# SJA1105Q_LAN8870_EVB_revA.net
KiCad netlist of a schematic drawn in Altium Designer
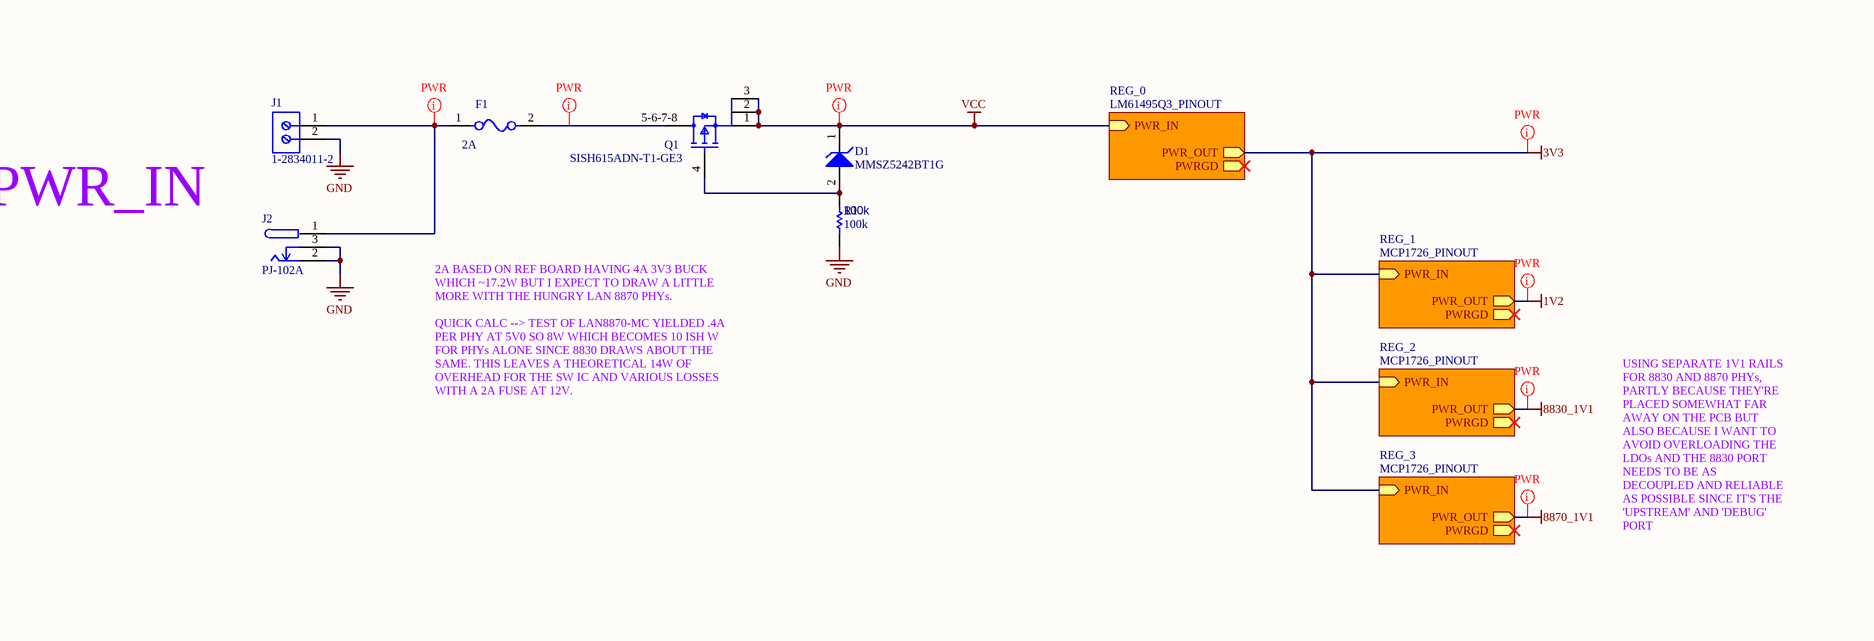
[diagram p0: SJA1105Q_LAN8870_EVB_revA.SchDoc, top left]
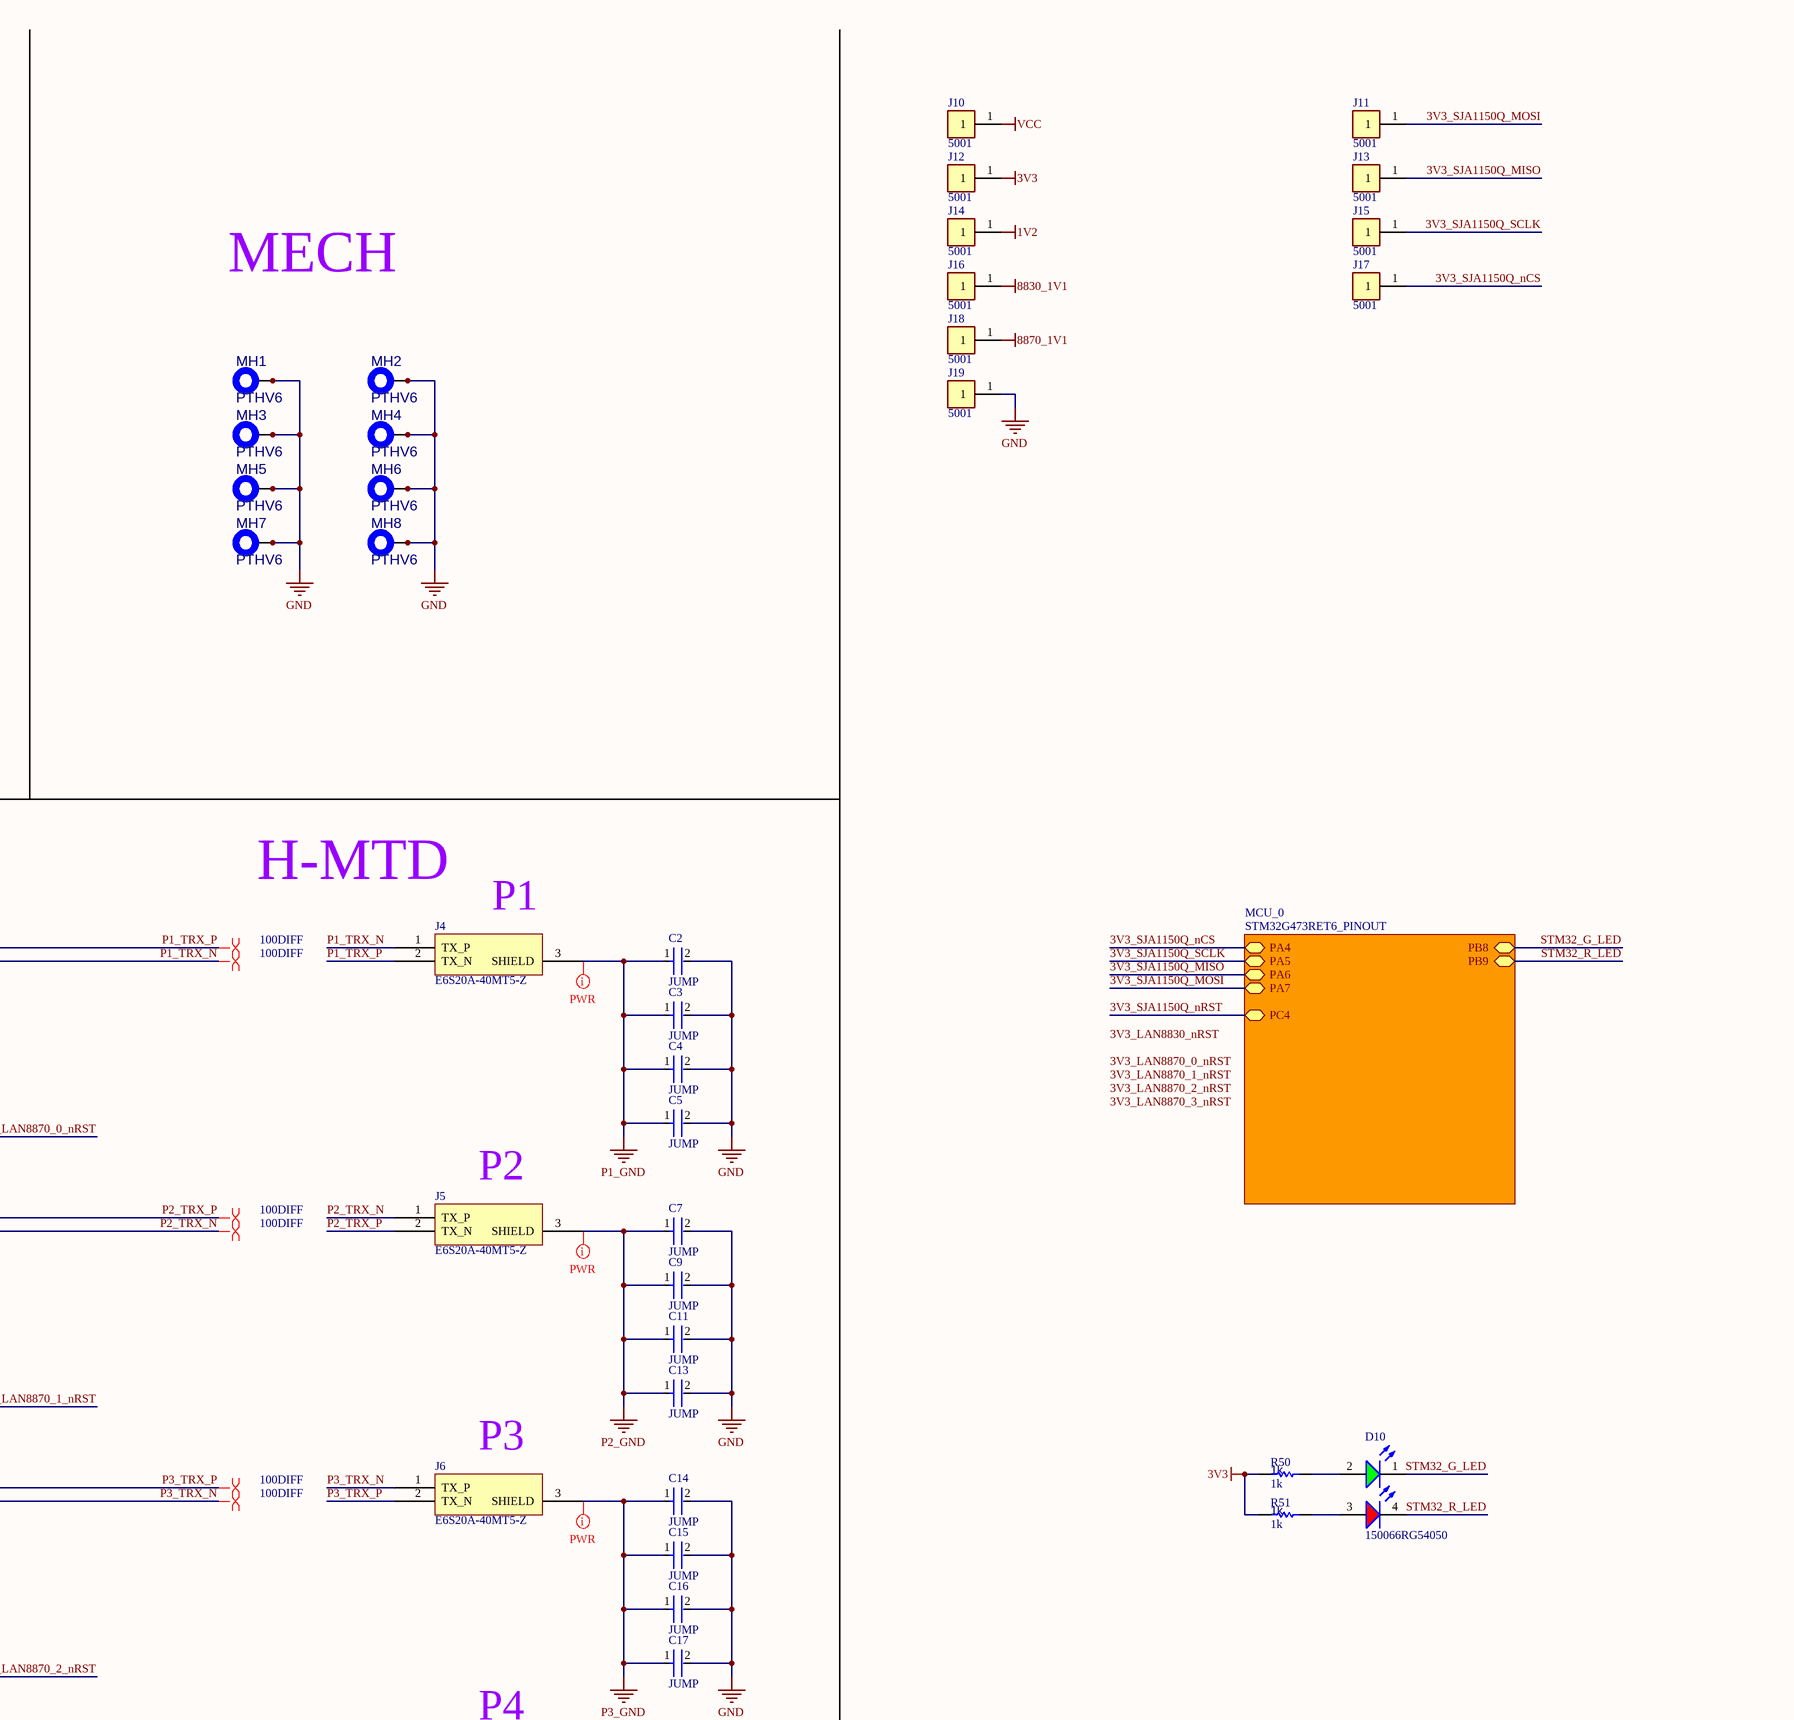
[diagram p1: SJA1105Q_LAN8870_EVB_revA.SchDoc, top right]
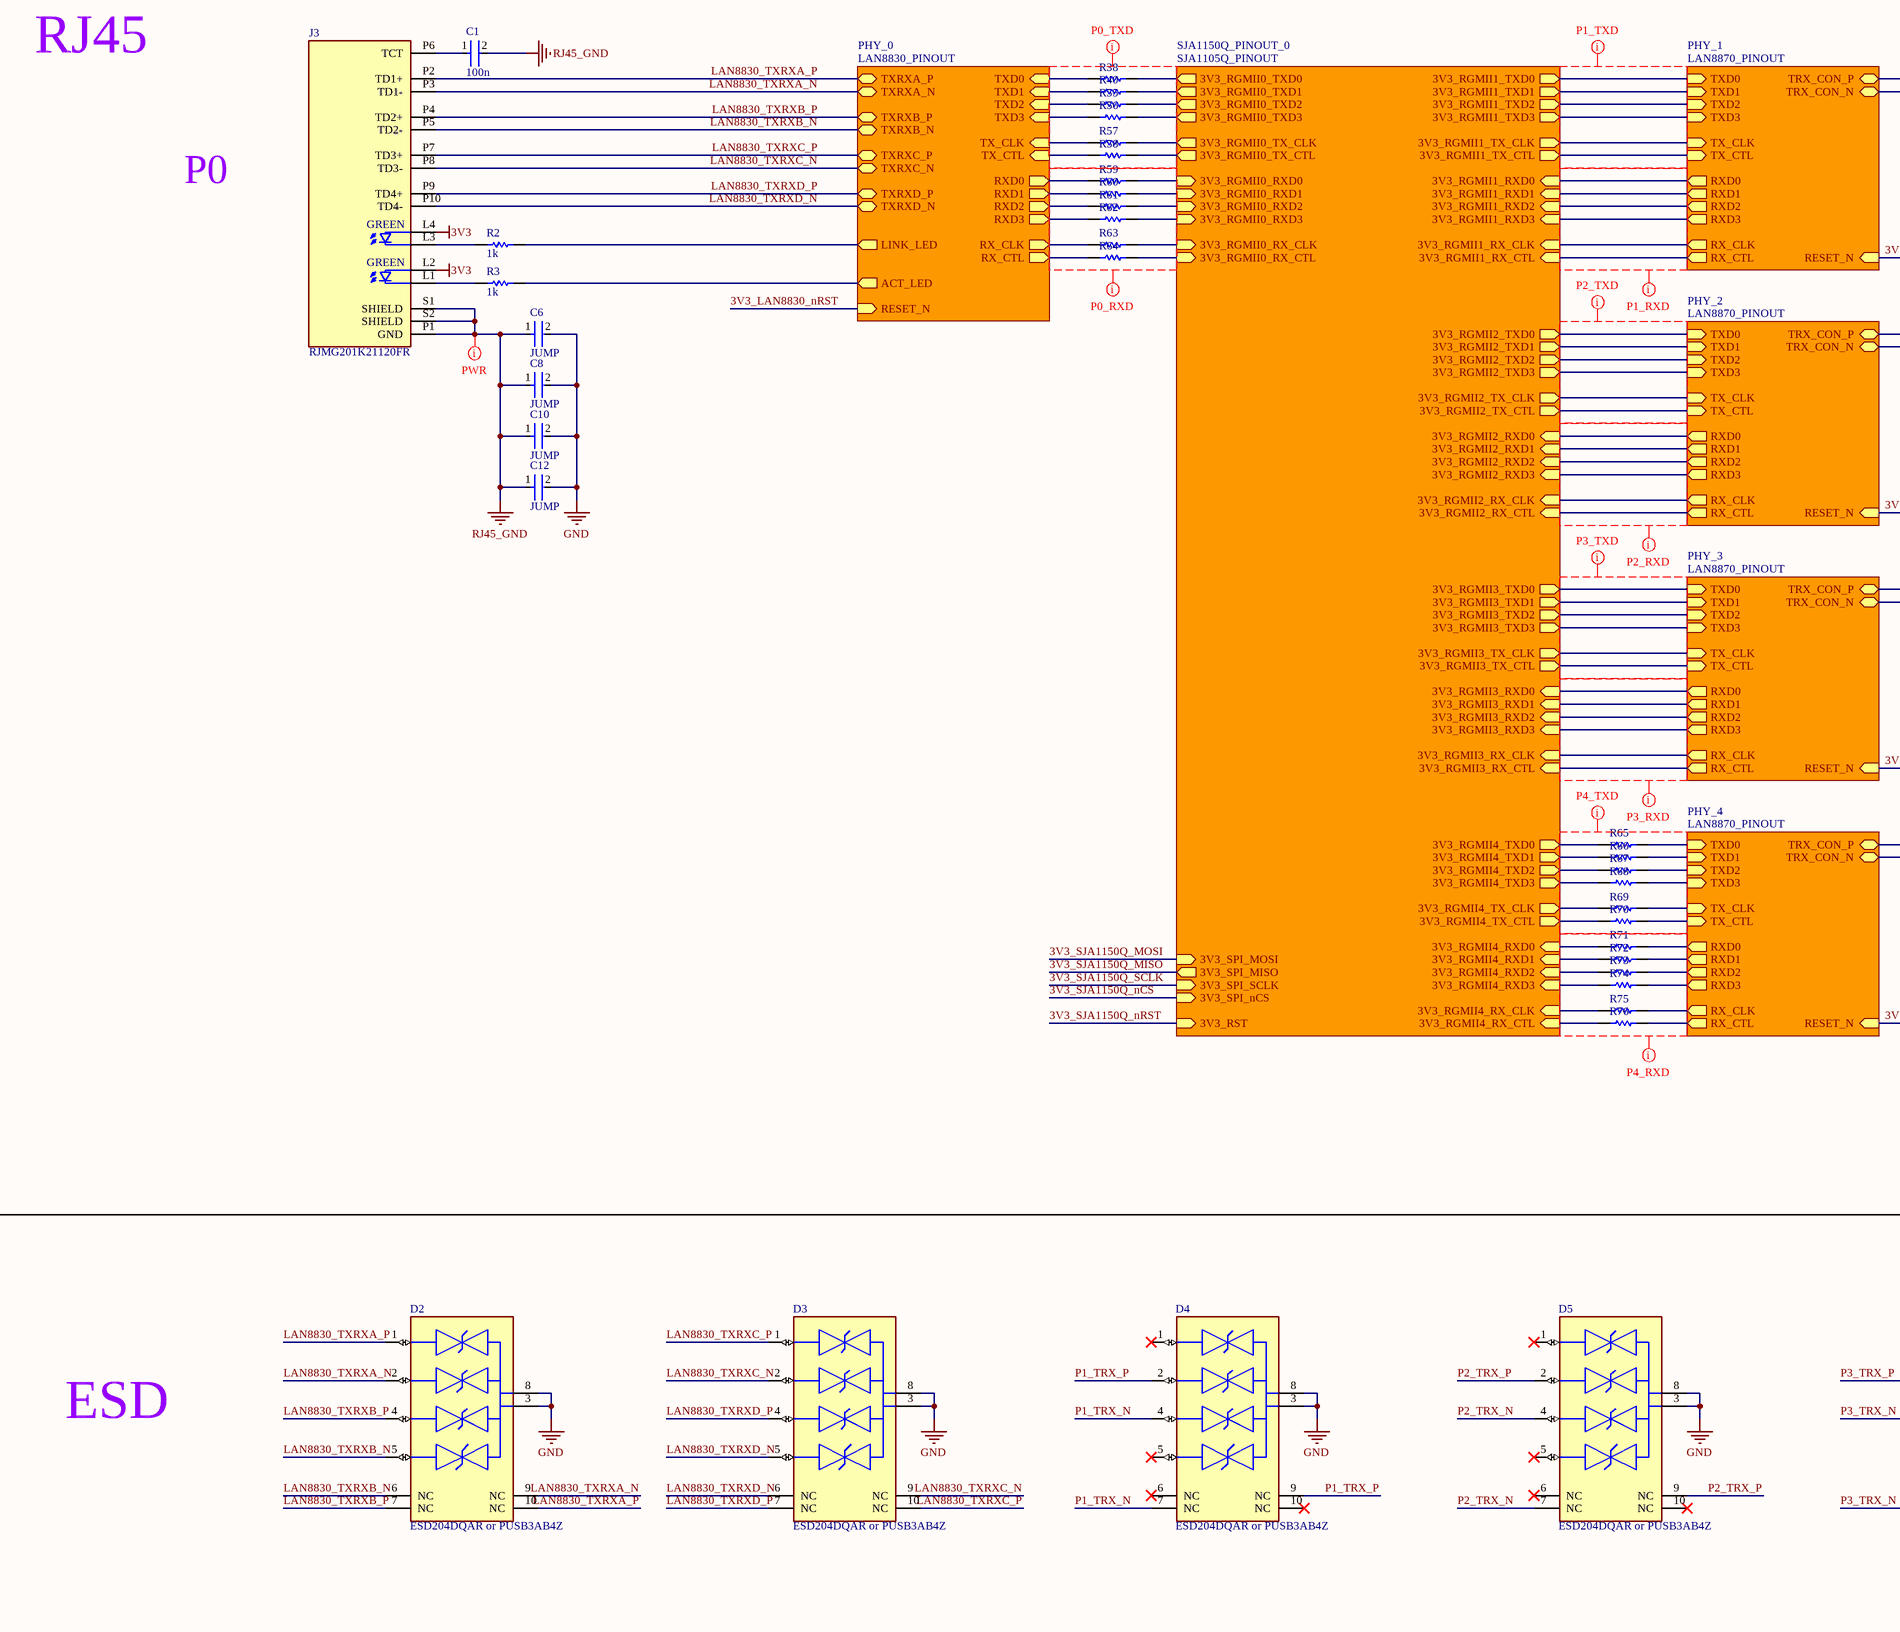
[diagram p2: SJA1105Q_LAN8870_EVB_revA.SchDoc, bottom left]
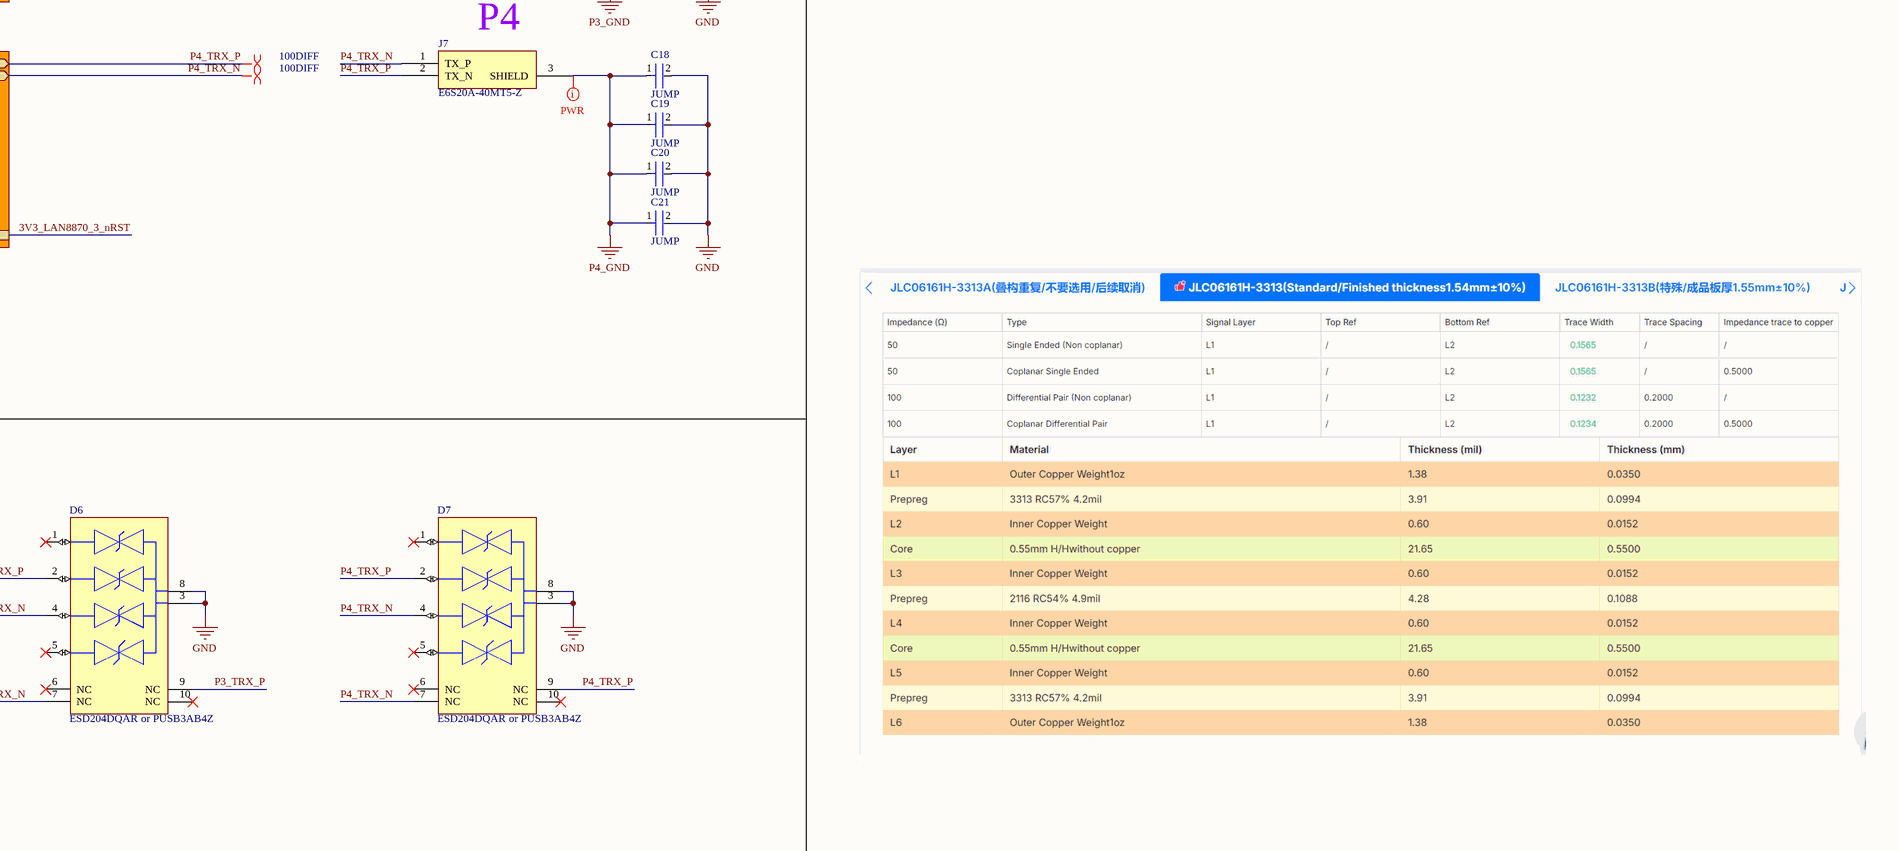
[diagram p3: SJA1105Q_LAN8870_EVB_revA.SchDoc, bottom right]

(export (version "E")
  (design (tool "Eeschema 10.0.6"))
  (components
    (comp (ref "C1")
      (value "100n")
      (footprint "FP-0402-L_1_0_0_05-W_0_5-IPC_A")
      (description "LARGE PADS, 0402 CAP, CHANGE COMMENT TO MATCH REAL P/N")
      (libsource (lib "Space Concordia") (part "b4654b650e69147ec39a6b967a45e02"))
    )
    (comp (ref "C2")
      (value "JUMP")
      (footprint "FP-0402-L_1_0_0_05-W_0_5-IPC_A")
      (description "LARGE PADS, 0402 CAP, CHANGE COMMENT TO MATCH REAL P/N")
      (libsource (lib "Space Concordia") (part "b4654b650e69147ec39a6b967a45e02"))
    )
    (comp (ref "C3")
      (value "JUMP")
      (footprint "FP-0402-L_1_0_0_05-W_0_5-IPC_A")
      (description "LARGE PADS, 0402 CAP, CHANGE COMMENT TO MATCH REAL P/N")
      (libsource (lib "Space Concordia") (part "b4654b650e69147ec39a6b967a45e02"))
    )
    (comp (ref "C4")
      (value "JUMP")
      (footprint "FP-0402-L_1_0_0_05-W_0_5-IPC_A")
      (description "LARGE PADS, 0402 CAP, CHANGE COMMENT TO MATCH REAL P/N")
      (libsource (lib "Space Concordia") (part "b4654b650e69147ec39a6b967a45e02"))
    )
    (comp (ref "C5")
      (value "JUMP")
      (footprint "FP-0402-L_1_0_0_05-W_0_5-IPC_A")
      (description "LARGE PADS, 0402 CAP, CHANGE COMMENT TO MATCH REAL P/N")
      (libsource (lib "Space Concordia") (part "b4654b650e69147ec39a6b967a45e02"))
    )
    (comp (ref "C6")
      (value "JUMP")
      (footprint "FP-0402-L_1_0_0_05-W_0_5-IPC_A")
      (description "LARGE PADS, 0402 CAP, CHANGE COMMENT TO MATCH REAL P/N")
      (libsource (lib "Space Concordia") (part "b4654b650e69147ec39a6b967a45e02"))
    )
    (comp (ref "C7")
      (value "JUMP")
      (footprint "FP-0402-L_1_0_0_05-W_0_5-IPC_A")
      (description "LARGE PADS, 0402 CAP, CHANGE COMMENT TO MATCH REAL P/N")
      (libsource (lib "Space Concordia") (part "b4654b650e69147ec39a6b967a45e02"))
    )
    (comp (ref "C8")
      (value "JUMP")
      (footprint "FP-0402-L_1_0_0_05-W_0_5-IPC_A")
      (description "LARGE PADS, 0402 CAP, CHANGE COMMENT TO MATCH REAL P/N")
      (libsource (lib "Space Concordia") (part "b4654b650e69147ec39a6b967a45e02"))
    )
    (comp (ref "C9")
      (value "JUMP")
      (footprint "FP-0402-L_1_0_0_05-W_0_5-IPC_A")
      (description "LARGE PADS, 0402 CAP, CHANGE COMMENT TO MATCH REAL P/N")
      (libsource (lib "Space Concordia") (part "b4654b650e69147ec39a6b967a45e02"))
    )
    (comp (ref "C10")
      (value "JUMP")
      (footprint "FP-0402-L_1_0_0_05-W_0_5-IPC_A")
      (description "LARGE PADS, 0402 CAP, CHANGE COMMENT TO MATCH REAL P/N")
      (libsource (lib "Space Concordia") (part "b4654b650e69147ec39a6b967a45e02"))
    )
    (comp (ref "C11")
      (value "JUMP")
      (footprint "FP-0402-L_1_0_0_05-W_0_5-IPC_A")
      (description "LARGE PADS, 0402 CAP, CHANGE COMMENT TO MATCH REAL P/N")
      (libsource (lib "Space Concordia") (part "b4654b650e69147ec39a6b967a45e02"))
    )
    (comp (ref "C12")
      (value "JUMP")
      (footprint "FP-0402-L_1_0_0_05-W_0_5-IPC_A")
      (description "LARGE PADS, 0402 CAP, CHANGE COMMENT TO MATCH REAL P/N")
      (libsource (lib "Space Concordia") (part "b4654b650e69147ec39a6b967a45e02"))
    )
    (comp (ref "C13")
      (value "JUMP")
      (footprint "FP-0402-L_1_0_0_05-W_0_5-IPC_A")
      (description "LARGE PADS, 0402 CAP, CHANGE COMMENT TO MATCH REAL P/N")
      (libsource (lib "Space Concordia") (part "b4654b650e69147ec39a6b967a45e02"))
    )
    (comp (ref "C14")
      (value "JUMP")
      (footprint "FP-0402-L_1_0_0_05-W_0_5-IPC_A")
      (description "LARGE PADS, 0402 CAP, CHANGE COMMENT TO MATCH REAL P/N")
      (libsource (lib "Space Concordia") (part "b4654b650e69147ec39a6b967a45e02"))
    )
    (comp (ref "C15")
      (value "JUMP")
      (footprint "FP-0402-L_1_0_0_05-W_0_5-IPC_A")
      (description "LARGE PADS, 0402 CAP, CHANGE COMMENT TO MATCH REAL P/N")
      (libsource (lib "Space Concordia") (part "b4654b650e69147ec39a6b967a45e02"))
    )
    (comp (ref "C16")
      (value "JUMP")
      (footprint "FP-0402-L_1_0_0_05-W_0_5-IPC_A")
      (description "LARGE PADS, 0402 CAP, CHANGE COMMENT TO MATCH REAL P/N")
      (libsource (lib "Space Concordia") (part "b4654b650e69147ec39a6b967a45e02"))
    )
    (comp (ref "C17")
      (value "JUMP")
      (footprint "FP-0402-L_1_0_0_05-W_0_5-IPC_A")
      (description "LARGE PADS, 0402 CAP, CHANGE COMMENT TO MATCH REAL P/N")
      (libsource (lib "Space Concordia") (part "b4654b650e69147ec39a6b967a45e02"))
    )
    (comp (ref "C18")
      (value "JUMP")
      (footprint "FP-0402-L_1_0_0_05-W_0_5-IPC_A")
      (description "LARGE PADS, 0402 CAP, CHANGE COMMENT TO MATCH REAL P/N")
      (libsource (lib "Space Concordia") (part "b4654b650e69147ec39a6b967a45e02"))
    )
    (comp (ref "C19")
      (value "JUMP")
      (footprint "FP-0402-L_1_0_0_05-W_0_5-IPC_A")
      (description "LARGE PADS, 0402 CAP, CHANGE COMMENT TO MATCH REAL P/N")
      (libsource (lib "Space Concordia") (part "b4654b650e69147ec39a6b967a45e02"))
    )
    (comp (ref "C20")
      (value "JUMP")
      (footprint "FP-0402-L_1_0_0_05-W_0_5-IPC_A")
      (description "LARGE PADS, 0402 CAP, CHANGE COMMENT TO MATCH REAL P/N")
      (libsource (lib "Space Concordia") (part "b4654b650e69147ec39a6b967a45e02"))
    )
    (comp (ref "C21")
      (value "JUMP")
      (footprint "FP-0402-L_1_0_0_05-W_0_5-IPC_A")
      (description "LARGE PADS, 0402 CAP, CHANGE COMMENT TO MATCH REAL P/N")
      (libsource (lib "Space Concordia") (part "b4654b650e69147ec39a6b967a45e02"))
    )
    (comp (ref "D1")
      (value "MMSZ5242BT1G")
      (footprint "ONSC-SOD-123-2-425-04_V")
      (description "Zener Voltage Regulator, 500 mW, 2-Pin SOD-123, Pb-Free, Tape and Reel")
      (fields (field (name "MANUFACTURER") "On Semiconductor"))
      (libsource (lib "Altium Content Vault") (part "ONSC-K1A2-2"))
    )
    (comp (ref "D2")
      (value "ESD204DQAR or PUSB3AB4Z")
      (footprint "FP-DQA0010A-MFG")
      (description "4-CHANNEL LOW-CAPACITANCE SURGE")
      (fields
        (field (name "MANUFACTURER") "Texas Instruments")
        (field (name "OCTOPART") "https://octopart.com/esd204dqar-texas+instruments-89917476")
      )
      (libsource (lib "Altium Content Vault") (part "1465e58c1818c7767b55926832f0bf5"))
    )
    (comp (ref "D3")
      (value "ESD204DQAR or PUSB3AB4Z")
      (footprint "FP-DQA0010A-MFG")
      (description "4-CHANNEL LOW-CAPACITANCE SURGE")
      (fields
        (field (name "MANUFACTURER") "Texas Instruments")
        (field (name "OCTOPART") "https://octopart.com/esd204dqar-texas+instruments-89917476")
      )
      (libsource (lib "Altium Content Vault") (part "1465e58c1818c7767b55926832f0bf5"))
    )
    (comp (ref "D4")
      (value "ESD204DQAR or PUSB3AB4Z")
      (footprint "FP-DQA0010A-MFG")
      (description "4-CHANNEL LOW-CAPACITANCE SURGE")
      (fields
        (field (name "MANUFACTURER") "Texas Instruments")
        (field (name "OCTOPART") "https://octopart.com/esd204dqar-texas+instruments-89917476")
      )
      (libsource (lib "Altium Content Vault") (part "1465e58c1818c7767b55926832f0bf5"))
    )
    (comp (ref "D5")
      (value "ESD204DQAR or PUSB3AB4Z")
      (footprint "FP-DQA0010A-MFG")
      (description "4-CHANNEL LOW-CAPACITANCE SURGE")
      (fields
        (field (name "MANUFACTURER") "Texas Instruments")
        (field (name "OCTOPART") "https://octopart.com/esd204dqar-texas+instruments-89917476")
      )
      (libsource (lib "Altium Content Vault") (part "1465e58c1818c7767b55926832f0bf5"))
    )
    (comp (ref "D6")
      (value "ESD204DQAR or PUSB3AB4Z")
      (footprint "FP-DQA0010A-MFG")
      (description "4-CHANNEL LOW-CAPACITANCE SURGE")
      (fields
        (field (name "MANUFACTURER") "Texas Instruments")
        (field (name "OCTOPART") "https://octopart.com/esd204dqar-texas+instruments-89917476")
      )
      (libsource (lib "Altium Content Vault") (part "1465e58c1818c7767b55926832f0bf5"))
    )
    (comp (ref "D7")
      (value "ESD204DQAR or PUSB3AB4Z")
      (footprint "FP-DQA0010A-MFG")
      (description "4-CHANNEL LOW-CAPACITANCE SURGE")
      (fields
        (field (name "MANUFACTURER") "Texas Instruments")
        (field (name "OCTOPART") "https://octopart.com/esd204dqar-texas+instruments-89917476")
      )
      (libsource (lib "Altium Content Vault") (part "1465e58c1818c7767b55926832f0bf5"))
    )
    (comp (ref "D10")
      (value "150066RG54050")
      (footprint "WL-SBCD_0606")
      (description "Led, Red/Grn, 180Mcd/230Mcd, 624Nm/525Nm Rohs Compliant: Yes")
      (fields (field (name "SOURCE") "rgled.SchLib"))
      (libsource (lib "Space Concordia") (part "CMP-004-00034-2"))
    )
    (comp (ref "F1")
      (value "2A")
      (footprint "FP-SF-1206FP-MFG")
      (description "FUSE BOARD MOUNT 2A 63VDC 1206")
      (libsource (lib "Altium Content Vault") (part "5bcf9b9f640e542cf0359d10258e979"))
    )
    (comp (ref "J1")
      (value "1-2834011-2")
      (footprint "1-2834011-2-Footprint-1")
      (description "Barrier Strip Terminal Block")
      (libsource (lib "Space Concordia") (part "1-2834011-2"))
    )
    (comp (ref "J2")
      (value "PJ-102A")
      (footprint "FP-PJ-102A-MFG")
      (description "PJ-102A 2.0 x 6.5 mm, 2.5 A, Horizontal, Through Hole, Tapered Pins, Dc Power Jack Connector")
      (libsource (lib "Altium Content Vault") (part "c639f672d24b5d70918fa8d934b95d1"))
    )
    (comp (ref "J3")
      (value "RJMG201K21120FR")
      (footprint "RJMG201K21120FR-Footprint-1")
      (description "Connector RJ45 Receptacle 8 Position Solder Straight Through Hole 1 Port Tray")
      (libsource (lib "Space Concordia") (part "RJMG201K21120FR"))
    )
    (comp (ref "J4")
      (value "E6S20A-40MT5-Z")
      (footprint "E6S20A-40MT5-Z-Footprint-1")
      (description "RF Connector, 2 Contact(s), Male, Panel Mount, Board And Panel Mount, Solder Terminal, Plug")
      (libsource (lib "Space Concordia") (part "E6S20A-40MT5-Z"))
    )
    (comp (ref "J5")
      (value "E6S20A-40MT5-Z")
      (footprint "E6S20A-40MT5-Z-Footprint-1")
      (description "RF Connector, 2 Contact(s), Male, Panel Mount, Board And Panel Mount, Solder Terminal, Plug")
      (libsource (lib "Space Concordia") (part "E6S20A-40MT5-Z"))
    )
    (comp (ref "J6")
      (value "E6S20A-40MT5-Z")
      (footprint "E6S20A-40MT5-Z-Footprint-1")
      (description "RF Connector, 2 Contact(s), Male, Panel Mount, Board And Panel Mount, Solder Terminal, Plug")
      (libsource (lib "Space Concordia") (part "E6S20A-40MT5-Z"))
    )
    (comp (ref "J7")
      (value "E6S20A-40MT5-Z")
      (footprint "E6S20A-40MT5-Z-Footprint-1")
      (description "RF Connector, 2 Contact(s), Male, Panel Mount, Board And Panel Mount, Solder Terminal, Plug")
      (libsource (lib "Space Concordia") (part "E6S20A-40MT5-Z"))
    )
    (comp (ref "J10")
      (value "5001")
      (footprint "FP-5001-MFG")
      (description "PC TEST POINT MINIATURE BLACK")
      (libsource (lib "Altium Content Vault") (part "1e4615820a309e3ce90f9e6d957b7fa"))
    )
    (comp (ref "J11")
      (value "5001")
      (footprint "FP-5001-MFG")
      (description "PC TEST POINT MINIATURE BLACK")
      (libsource (lib "Altium Content Vault") (part "1e4615820a309e3ce90f9e6d957b7fa"))
    )
    (comp (ref "J12")
      (value "5001")
      (footprint "FP-5001-MFG")
      (description "PC TEST POINT MINIATURE BLACK")
      (libsource (lib "Altium Content Vault") (part "1e4615820a309e3ce90f9e6d957b7fa"))
    )
    (comp (ref "J13")
      (value "5001")
      (footprint "FP-5001-MFG")
      (description "PC TEST POINT MINIATURE BLACK")
      (libsource (lib "Altium Content Vault") (part "1e4615820a309e3ce90f9e6d957b7fa"))
    )
    (comp (ref "J14")
      (value "5001")
      (footprint "FP-5001-MFG")
      (description "PC TEST POINT MINIATURE BLACK")
      (libsource (lib "Altium Content Vault") (part "1e4615820a309e3ce90f9e6d957b7fa"))
    )
    (comp (ref "J15")
      (value "5001")
      (footprint "FP-5001-MFG")
      (description "PC TEST POINT MINIATURE BLACK")
      (libsource (lib "Altium Content Vault") (part "1e4615820a309e3ce90f9e6d957b7fa"))
    )
    (comp (ref "J16")
      (value "5001")
      (footprint "FP-5001-MFG")
      (description "PC TEST POINT MINIATURE BLACK")
      (libsource (lib "Altium Content Vault") (part "1e4615820a309e3ce90f9e6d957b7fa"))
    )
    (comp (ref "J17")
      (value "5001")
      (footprint "FP-5001-MFG")
      (description "PC TEST POINT MINIATURE BLACK")
      (libsource (lib "Altium Content Vault") (part "1e4615820a309e3ce90f9e6d957b7fa"))
    )
    (comp (ref "J18")
      (value "5001")
      (footprint "FP-5001-MFG")
      (description "PC TEST POINT MINIATURE BLACK")
      (libsource (lib "Altium Content Vault") (part "1e4615820a309e3ce90f9e6d957b7fa"))
    )
    (comp (ref "J19")
      (value "5001")
      (footprint "FP-5001-MFG")
      (description "PC TEST POINT MINIATURE BLACK")
      (libsource (lib "Altium Content Vault") (part "1e4615820a309e3ce90f9e6d957b7fa"))
    )
    (comp (ref "MH1")
      (value "PTHV6")
      (footprint "PTHV6 M2")
      (libsource (lib "Space Concordia") (part "PTHV6"))
    )
    (comp (ref "MH2")
      (value "PTHV6")
      (footprint "PTHV6 M2")
      (libsource (lib "Space Concordia") (part "PTHV6"))
    )
    (comp (ref "MH3")
      (value "PTHV6")
      (footprint "PTHV6 M2")
      (libsource (lib "Space Concordia") (part "PTHV6"))
    )
    (comp (ref "MH4")
      (value "PTHV6")
      (footprint "PTHV6 M2")
      (libsource (lib "Space Concordia") (part "PTHV6"))
    )
    (comp (ref "MH5")
      (value "PTHV6")
      (footprint "PTHV6 M2")
      (libsource (lib "Space Concordia") (part "PTHV6"))
    )
    (comp (ref "MH6")
      (value "PTHV6")
      (footprint "PTHV6 M2")
      (libsource (lib "Space Concordia") (part "PTHV6"))
    )
    (comp (ref "MH7")
      (value "PTHV6")
      (footprint "PTHV6 M2")
      (libsource (lib "Space Concordia") (part "PTHV6"))
    )
    (comp (ref "MH8")
      (value "PTHV6")
      (footprint "PTHV6 M2")
      (libsource (lib "Space Concordia") (part "PTHV6"))
    )
    (comp (ref "Q1")
      (value "SISH615ADN-T1-GE3")
      (footprint "SISH615ADN-T1-GE3-Footprint-1")
      (description "Trans MOSFET P-CH 20V 22.1A 8-Pin PowerPAK 1212 EP T/R")
      (libsource (lib "Space Concordia") (part "CMP-013-00036-4"))
    )
    (comp (ref "R1")
      (value "100k")
      (footprint "R0603B")
      (description "Resistor")
      (fields (field (name "ALTIUM_VALUE") "100k"))
      (libsource (lib "Space Concordia") (part "Resistor"))
    )
    (comp (ref "R2")
      (value "1k")
      (footprint "R0603B")
      (description "Resistor")
      (libsource (lib "Space Concordia") (part "Resistor"))
    )
    (comp (ref "R3")
      (value "1k")
      (footprint "R0603B")
      (description "Resistor")
      (libsource (lib "Space Concordia") (part "Resistor"))
    )
    (comp (ref "R38")
      (value "0402 JUMPER")
      (footprint "RESC1005X40X25ML05T05")
      (description "READ THE NAME")
      (libsource (lib "Space Concordia") (part "CMP-009-00206-2"))
    )
    (comp (ref "R40")
      (value "0402 JUMPER")
      (footprint "RESC1005X40X25ML05T05")
      (description "READ THE NAME")
      (libsource (lib "Space Concordia") (part "CMP-009-00206-2"))
    )
    (comp (ref "R50")
      (value "1k")
      (footprint "R0603B")
      (description "Resistor")
      (fields (field (name "ALTIUM_VALUE") "1k"))
      (libsource (lib "Space Concordia") (part "Resistor"))
    )
    (comp (ref "R51")
      (value "1k")
      (footprint "R0603B")
      (description "Resistor")
      (fields (field (name "ALTIUM_VALUE") "1k"))
      (libsource (lib "Space Concordia") (part "Resistor"))
    )
    (comp (ref "R55")
      (value "0402 JUMPER")
      (footprint "RESC1005X40X25ML05T05")
      (description "READ THE NAME")
      (libsource (lib "Space Concordia") (part "CMP-009-00206-2"))
    )
    (comp (ref "R56")
      (value "0402 JUMPER")
      (footprint "RESC1005X40X25ML05T05")
      (description "READ THE NAME")
      (libsource (lib "Space Concordia") (part "CMP-009-00206-2"))
    )
    (comp (ref "R57")
      (value "0402 JUMPER")
      (footprint "RESC1005X40X25ML05T05")
      (description "READ THE NAME")
      (libsource (lib "Space Concordia") (part "CMP-009-00206-2"))
    )
    (comp (ref "R58")
      (value "0402 JUMPER")
      (footprint "RESC1005X40X25ML05T05")
      (description "READ THE NAME")
      (libsource (lib "Space Concordia") (part "CMP-009-00206-2"))
    )
    (comp (ref "R59")
      (value "0402 JUMPER")
      (footprint "RESC1005X40X25ML05T05")
      (description "READ THE NAME")
      (libsource (lib "Space Concordia") (part "CMP-009-00206-2"))
    )
    (comp (ref "R60")
      (value "0402 JUMPER")
      (footprint "RESC1005X40X25ML05T05")
      (description "READ THE NAME")
      (libsource (lib "Space Concordia") (part "CMP-009-00206-2"))
    )
    (comp (ref "R61")
      (value "0402 JUMPER")
      (footprint "RESC1005X40X25ML05T05")
      (description "READ THE NAME")
      (libsource (lib "Space Concordia") (part "CMP-009-00206-2"))
    )
    (comp (ref "R62")
      (value "0402 JUMPER")
      (footprint "RESC1005X40X25ML05T05")
      (description "READ THE NAME")
      (libsource (lib "Space Concordia") (part "CMP-009-00206-2"))
    )
    (comp (ref "R63")
      (value "0402 JUMPER")
      (footprint "RESC1005X40X25ML05T05")
      (description "READ THE NAME")
      (libsource (lib "Space Concordia") (part "CMP-009-00206-2"))
    )
    (comp (ref "R64")
      (value "0402 JUMPER")
      (footprint "RESC1005X40X25ML05T05")
      (description "READ THE NAME")
      (libsource (lib "Space Concordia") (part "CMP-009-00206-2"))
    )
    (comp (ref "R65")
      (value "0402 JUMPER")
      (footprint "RESC1005X40X25ML05T05")
      (description "READ THE NAME")
      (libsource (lib "Space Concordia") (part "CMP-009-00206-2"))
    )
    (comp (ref "R66")
      (value "0402 JUMPER")
      (footprint "RESC1005X40X25ML05T05")
      (description "READ THE NAME")
      (libsource (lib "Space Concordia") (part "CMP-009-00206-2"))
    )
    (comp (ref "R67")
      (value "0402 JUMPER")
      (footprint "RESC1005X40X25ML05T05")
      (description "READ THE NAME")
      (libsource (lib "Space Concordia") (part "CMP-009-00206-2"))
    )
    (comp (ref "R68")
      (value "0402 JUMPER")
      (footprint "RESC1005X40X25ML05T05")
      (description "READ THE NAME")
      (libsource (lib "Space Concordia") (part "CMP-009-00206-2"))
    )
    (comp (ref "R69")
      (value "0402 JUMPER")
      (footprint "RESC1005X40X25ML05T05")
      (description "READ THE NAME")
      (libsource (lib "Space Concordia") (part "CMP-009-00206-2"))
    )
    (comp (ref "R70")
      (value "0402 JUMPER")
      (footprint "RESC1005X40X25ML05T05")
      (description "READ THE NAME")
      (libsource (lib "Space Concordia") (part "CMP-009-00206-2"))
    )
    (comp (ref "R71")
      (value "0402 JUMPER")
      (footprint "RESC1005X40X25ML05T05")
      (description "READ THE NAME")
      (libsource (lib "Space Concordia") (part "CMP-009-00206-2"))
    )
    (comp (ref "R72")
      (value "0402 JUMPER")
      (footprint "RESC1005X40X25ML05T05")
      (description "READ THE NAME")
      (libsource (lib "Space Concordia") (part "CMP-009-00206-2"))
    )
    (comp (ref "R73")
      (value "0402 JUMPER")
      (footprint "RESC1005X40X25ML05T05")
      (description "READ THE NAME")
      (libsource (lib "Space Concordia") (part "CMP-009-00206-2"))
    )
    (comp (ref "R74")
      (value "0402 JUMPER")
      (footprint "RESC1005X40X25ML05T05")
      (description "READ THE NAME")
      (libsource (lib "Space Concordia") (part "CMP-009-00206-2"))
    )
    (comp (ref "R75")
      (value "0402 JUMPER")
      (footprint "RESC1005X40X25ML05T05")
      (description "READ THE NAME")
      (libsource (lib "Space Concordia") (part "CMP-009-00206-2"))
    )
    (comp (ref "R76")
      (value "0402 JUMPER")
      (footprint "RESC1005X40X25ML05T05")
      (description "READ THE NAME")
      (libsource (lib "Space Concordia") (part "CMP-009-00206-2"))
    )
  )
  (nets
    (net (code "6") (name "/3V3_RGMII0_RXD0") (class "Default")
      (node (ref "R59") (pin "2") (pinfunction "2_2") (pintype "passive"))
    )
    (net (code "7") (name "/3V3_RGMII0_RXD1") (class "Default")
      (node (ref "R60") (pin "2") (pinfunction "2_2") (pintype "passive"))
    )
    (net (code "8") (name "/3V3_RGMII0_RXD2") (class "Default")
      (node (ref "R61") (pin "2") (pinfunction "2_2") (pintype "passive"))
    )
    (net (code "9") (name "/3V3_RGMII0_RXD3") (class "Default")
      (node (ref "R62") (pin "2") (pinfunction "2_2") (pintype "passive"))
    )
    (net (code "10") (name "/3V3_RGMII0_RX_CLK") (class "Default")
      (node (ref "R63") (pin "2") (pinfunction "2_2") (pintype "passive"))
    )
    (net (code "11") (name "/3V3_RGMII0_RX_CTL") (class "Default")
      (node (ref "R64") (pin "2") (pinfunction "2_2") (pintype "passive"))
    )
    (net (code "12") (name "/3V3_RGMII0_TXD0") (class "Default")
      (node (ref "R38") (pin "2") (pinfunction "2_2") (pintype "passive"))
    )
    (net (code "13") (name "/3V3_RGMII0_TXD1") (class "Default")
      (node (ref "R40") (pin "2") (pinfunction "2_2") (pintype "passive"))
    )
    (net (code "14") (name "/3V3_RGMII0_TXD2") (class "Default")
      (node (ref "R55") (pin "2") (pinfunction "2_2") (pintype "passive"))
    )
    (net (code "15") (name "/3V3_RGMII0_TXD3") (class "Default")
      (node (ref "R56") (pin "2") (pinfunction "2_2") (pintype "passive"))
    )
    (net (code "16") (name "/3V3_RGMII0_TX_CLK") (class "Default")
      (node (ref "R57") (pin "2") (pinfunction "2_2") (pintype "passive"))
    )
    (net (code "17") (name "/3V3_RGMII0_TX_CTL") (class "Default")
      (node (ref "R58") (pin "2") (pinfunction "2_2") (pintype "passive"))
    )
    (net (code "36") (name "/3V3_RGMII4_RXD0") (class "Default")
      (node (ref "R71") (pin "1") (pinfunction "1_1") (pintype "passive"))
    )
    (net (code "37") (name "/3V3_RGMII4_RXD1") (class "Default")
      (node (ref "R72") (pin "1") (pinfunction "1_1") (pintype "passive"))
    )
    (net (code "38") (name "/3V3_RGMII4_RXD2") (class "Default")
      (node (ref "R73") (pin "1") (pinfunction "1_1") (pintype "passive"))
    )
    (net (code "39") (name "/3V3_RGMII4_RXD3") (class "Default")
      (node (ref "R74") (pin "1") (pinfunction "1_1") (pintype "passive"))
    )
    (net (code "40") (name "/3V3_RGMII4_RX_CLK") (class "Default")
      (node (ref "R75") (pin "1") (pinfunction "1_1") (pintype "passive"))
    )
    (net (code "41") (name "/3V3_RGMII4_RX_CTL") (class "Default")
      (node (ref "R76") (pin "1") (pinfunction "1_1") (pintype "passive"))
    )
    (net (code "42") (name "/3V3_RGMII4_TXD0") (class "Default")
      (node (ref "R65") (pin "1") (pinfunction "1_1") (pintype "passive"))
    )
    (net (code "43") (name "/3V3_RGMII4_TXD1") (class "Default")
      (node (ref "R66") (pin "1") (pinfunction "1_1") (pintype "passive"))
    )
    (net (code "44") (name "/3V3_RGMII4_TXD2") (class "Default")
      (node (ref "R67") (pin "1") (pinfunction "1_1") (pintype "passive"))
    )
    (net (code "45") (name "/3V3_RGMII4_TXD3") (class "Default")
      (node (ref "R68") (pin "1") (pinfunction "1_1") (pintype "passive"))
    )
    (net (code "46") (name "/3V3_RGMII4_TX_CLK") (class "Default")
      (node (ref "R69") (pin "1") (pinfunction "1_1") (pintype "passive"))
    )
    (net (code "47") (name "/3V3_RGMII4_TX_CTL") (class "Default")
      (node (ref "R70") (pin "1") (pinfunction "1_1") (pintype "passive"))
    )
    (net (code "48") (name "/3V3_SJA1150Q_MISO") (class "Default")
      (node (ref "J13") (pin "1") (pinfunction "1_1") (pintype "passive"))
    )
    (net (code "49") (name "/3V3_SJA1150Q_MOSI") (class "Default")
      (node (ref "J11") (pin "1") (pinfunction "1_1") (pintype "passive"))
    )
    (net (code "50") (name "/3V3_SJA1150Q_SCLK") (class "Default")
      (node (ref "J15") (pin "1") (pinfunction "1_1") (pintype "passive"))
    )
    (net (code "51") (name "/3V3_SJA1150Q_nCS") (class "Default")
      (node (ref "J17") (pin "1") (pinfunction "1_1") (pintype "passive"))
    )
    (net (code "53") (name "/ACT_LED") (class "Default")
      (node (ref "R3") (pin "1") (pinfunction "1_1") (pintype "passive"))
    )
    (net (code "54") (name "/LAN8830_TXRXA_N") (class "Default")
      (node (ref "D2") (pin "2") (pinfunction "IO2_2") (pintype "bidirectional"))
      (node (ref "D2") (pin "9") (pinfunction "NC_9") (pintype "passive"))
      (node (ref "J3") (pin "P3") (pinfunction "TD1-_P3") (pintype "passive"))
    )
    (net (code "55") (name "/LAN8830_TXRXA_P") (class "Default")
      (node (ref "D2") (pin "1") (pinfunction "IO1_1") (pintype "bidirectional"))
      (node (ref "D2") (pin "10") (pinfunction "NC_10") (pintype "passive"))
      (node (ref "J3") (pin "P2") (pinfunction "TD1+_P2") (pintype "passive"))
    )
    (net (code "56") (name "/LAN8830_TXRXB_N") (class "Default")
      (node (ref "D2") (pin "5") (pinfunction "IO4_5") (pintype "bidirectional"))
      (node (ref "D2") (pin "6") (pinfunction "NC_6") (pintype "passive"))
      (node (ref "J3") (pin "P5") (pinfunction "TD2-_P5") (pintype "passive"))
    )
    (net (code "57") (name "/LAN8830_TXRXB_P") (class "Default")
      (node (ref "D2") (pin "4") (pinfunction "IO3_4") (pintype "bidirectional"))
      (node (ref "D2") (pin "7") (pinfunction "NC_7") (pintype "passive"))
      (node (ref "J3") (pin "P4") (pinfunction "TD2+_P4") (pintype "passive"))
    )
    (net (code "58") (name "/LAN8830_TXRXC_N") (class "Default")
      (node (ref "D3") (pin "2") (pinfunction "IO2_2") (pintype "bidirectional"))
      (node (ref "D3") (pin "9") (pinfunction "NC_9") (pintype "passive"))
      (node (ref "J3") (pin "P8") (pinfunction "TD3-_P8") (pintype "passive"))
    )
    (net (code "59") (name "/LAN8830_TXRXC_P") (class "Default")
      (node (ref "D3") (pin "1") (pinfunction "IO1_1") (pintype "bidirectional"))
      (node (ref "D3") (pin "10") (pinfunction "NC_10") (pintype "passive"))
      (node (ref "J3") (pin "P7") (pinfunction "TD3+_P7") (pintype "passive"))
    )
    (net (code "60") (name "/LAN8830_TXRXD_N") (class "Default")
      (node (ref "D3") (pin "5") (pinfunction "IO4_5") (pintype "bidirectional"))
      (node (ref "D3") (pin "6") (pinfunction "NC_6") (pintype "passive"))
      (node (ref "J3") (pin "P10") (pinfunction "TD4-_P10") (pintype "passive"))
    )
    (net (code "61") (name "/LAN8830_TXRXD_P") (class "Default")
      (node (ref "D3") (pin "4") (pinfunction "IO3_4") (pintype "bidirectional"))
      (node (ref "D3") (pin "7") (pinfunction "NC_7") (pintype "passive"))
      (node (ref "J3") (pin "P9") (pinfunction "TD4+_P9") (pintype "passive"))
    )
    (net (code "62") (name "/LINK_LED") (class "Default")
      (node (ref "R2") (pin "1") (pinfunction "1_1") (pintype "passive"))
    )
    (net (code "63") (name "/P1_TRX_N") (class "Default")
      (node (ref "D4") (pin "4") (pinfunction "IO3_4") (pintype "bidirectional"))
      (node (ref "D4") (pin "7") (pinfunction "NC_7") (pintype "passive"))
      (node (ref "J4") (pin "1") (pinfunction "TX_P_1") (pintype "passive"))
    )
    (net (code "64") (name "/P1_TRX_P") (class "Default")
      (node (ref "D4") (pin "2") (pinfunction "IO2_2") (pintype "bidirectional"))
      (node (ref "D4") (pin "9") (pinfunction "NC_9") (pintype "passive"))
      (node (ref "J4") (pin "2") (pinfunction "TX_N_2") (pintype "passive"))
    )
    (net (code "65") (name "/P2_TRX_N") (class "Default")
      (node (ref "D5") (pin "4") (pinfunction "IO3_4") (pintype "bidirectional"))
      (node (ref "D5") (pin "7") (pinfunction "NC_7") (pintype "passive"))
      (node (ref "J5") (pin "1") (pinfunction "TX_P_1") (pintype "passive"))
    )
    (net (code "66") (name "/P2_TRX_P") (class "Default")
      (node (ref "D5") (pin "2") (pinfunction "IO2_2") (pintype "bidirectional"))
      (node (ref "D5") (pin "9") (pinfunction "NC_9") (pintype "passive"))
      (node (ref "J5") (pin "2") (pinfunction "TX_N_2") (pintype "passive"))
    )
    (net (code "67") (name "/P3_TRX_N") (class "Default")
      (node (ref "D6") (pin "4") (pinfunction "IO3_4") (pintype "bidirectional"))
      (node (ref "D6") (pin "7") (pinfunction "NC_7") (pintype "passive"))
      (node (ref "J6") (pin "1") (pinfunction "TX_P_1") (pintype "passive"))
    )
    (net (code "68") (name "/P3_TRX_P") (class "Default")
      (node (ref "D6") (pin "2") (pinfunction "IO2_2") (pintype "bidirectional"))
      (node (ref "D6") (pin "9") (pinfunction "NC_9") (pintype "passive"))
      (node (ref "J6") (pin "2") (pinfunction "TX_N_2") (pintype "passive"))
    )
    (net (code "69") (name "/P4_TRX_N") (class "Default")
      (node (ref "D7") (pin "4") (pinfunction "IO3_4") (pintype "bidirectional"))
      (node (ref "D7") (pin "7") (pinfunction "NC_7") (pintype "passive"))
      (node (ref "J7") (pin "1") (pinfunction "TX_P_1") (pintype "passive"))
    )
    (net (code "70") (name "/P4_TRX_P") (class "Default")
      (node (ref "D7") (pin "2") (pinfunction "IO2_2") (pintype "bidirectional"))
      (node (ref "D7") (pin "9") (pinfunction "NC_9") (pintype "passive"))
      (node (ref "J7") (pin "2") (pinfunction "TX_N_2") (pintype "passive"))
    )
    (net (code "75") (name "/RXD0") (class "Default")
      (node (ref "R71") (pin "2") (pinfunction "2_2") (pintype "passive"))
    )
    (net (code "79") (name "/RXD0_4") (class "Default")
      (node (ref "R59") (pin "1") (pinfunction "1_1") (pintype "passive"))
    )
    (net (code "80") (name "/RXD1") (class "Default")
      (node (ref "R72") (pin "2") (pinfunction "2_2") (pintype "passive"))
    )
    (net (code "84") (name "/RXD1_4") (class "Default")
      (node (ref "R60") (pin "1") (pinfunction "1_1") (pintype "passive"))
    )
    (net (code "85") (name "/RXD2") (class "Default")
      (node (ref "R73") (pin "2") (pinfunction "2_2") (pintype "passive"))
    )
    (net (code "86") (name "/RXD2_1") (class "Default")
      (node (ref "R61") (pin "1") (pinfunction "1_1") (pintype "passive"))
    )
    (net (code "90") (name "/RXD3") (class "Default")
      (node (ref "R74") (pin "2") (pinfunction "2_2") (pintype "passive"))
    )
    (net (code "91") (name "/RXD3_1") (class "Default")
      (node (ref "R62") (pin "1") (pinfunction "1_1") (pintype "passive"))
    )
    (net (code "95") (name "/RX_CLK") (class "Default")
      (node (ref "R75") (pin "2") (pinfunction "2_2") (pintype "passive"))
    )
    (net (code "96") (name "/RX_CLK_1") (class "Default")
      (node (ref "R63") (pin "1") (pinfunction "1_1") (pintype "passive"))
    )
    (net (code "100") (name "/RX_CTL") (class "Default")
      (node (ref "R76") (pin "2") (pinfunction "2_2") (pintype "passive"))
    )
    (net (code "101") (name "/RX_CTL_1") (class "Default")
      (node (ref "R64") (pin "1") (pinfunction "1_1") (pintype "passive"))
    )
    (net (code "105") (name "/STM32_G_LED") (class "Default")
      (node (ref "D10") (pin "1") (pinfunction "K_1") (pintype "passive"))
    )
    (net (code "106") (name "/STM32_R_LED") (class "Default")
      (node (ref "D10") (pin "4") (pinfunction "K_4") (pintype "passive"))
    )
    (net (code "107") (name "/TXD0") (class "Default")
      (node (ref "R65") (pin "2") (pinfunction "2_2") (pintype "passive"))
    )
    (net (code "108") (name "/TXD0_1") (class "Default")
      (node (ref "R38") (pin "1") (pinfunction "1_1") (pintype "passive"))
    )
    (net (code "109") (name "/TXD1") (class "Default")
      (node (ref "R66") (pin "2") (pinfunction "2_2") (pintype "passive"))
    )
    (net (code "110") (name "/TXD1_1") (class "Default")
      (node (ref "R40") (pin "1") (pinfunction "1_1") (pintype "passive"))
    )
    (net (code "111") (name "/TXD2") (class "Default")
      (node (ref "R67") (pin "2") (pinfunction "2_2") (pintype "passive"))
    )
    (net (code "112") (name "/TXD2_1") (class "Default")
      (node (ref "R55") (pin "1") (pinfunction "1_1") (pintype "passive"))
    )
    (net (code "113") (name "/TXD3") (class "Default")
      (node (ref "R68") (pin "2") (pinfunction "2_2") (pintype "passive"))
    )
    (net (code "114") (name "/TXD3_1") (class "Default")
      (node (ref "R56") (pin "1") (pinfunction "1_1") (pintype "passive"))
    )
    (net (code "115") (name "/TX_CLK") (class "Default")
      (node (ref "R69") (pin "2") (pinfunction "2_2") (pintype "passive"))
    )
    (net (code "116") (name "/TX_CLK_1") (class "Default")
      (node (ref "R57") (pin "1") (pinfunction "1_1") (pintype "passive"))
    )
    (net (code "117") (name "/TX_CTL") (class "Default")
      (node (ref "R70") (pin "2") (pinfunction "2_2") (pintype "passive"))
    )
    (net (code "118") (name "/TX_CTL_1") (class "Default")
      (node (ref "R58") (pin "1") (pinfunction "1_1") (pintype "passive"))
    )
    (net (code "119") (name "1V2") (class "Default")
      (node (ref "J14") (pin "1") (pinfunction "1_1") (pintype "passive"))
    )
    (net (code "120") (name "3V3") (class "Default")
      (node (ref "J12") (pin "1") (pinfunction "1_1") (pintype "passive"))
      (node (ref "J3") (pin "L2") (pinfunction "L2_L2") (pintype "passive"))
      (node (ref "J3") (pin "L4") (pinfunction "L4_L4") (pintype "passive"))
      (node (ref "R50") (pin "2") (pinfunction "2_2") (pintype "passive"))
      (node (ref "R51") (pin "2") (pinfunction "2_2") (pintype "passive"))
    )
    (net (code "121") (name "8830_1V1") (class "Default")
      (node (ref "J16") (pin "1") (pinfunction "1_1") (pintype "passive"))
    )
    (net (code "122") (name "8870_1V1") (class "Default")
      (node (ref "J18") (pin "1") (pinfunction "1_1") (pintype "passive"))
    )
    (net (code "123") (name "GND") (class "Default")
      (node (ref "C10") (pin "2") (pinfunction "2_2") (pintype "passive"))
      (node (ref "C11") (pin "2") (pinfunction "2_2") (pintype "passive"))
      (node (ref "C12") (pin "2") (pinfunction "2_2") (pintype "passive"))
      (node (ref "C13") (pin "2") (pinfunction "2_2") (pintype "passive"))
      (node (ref "C14") (pin "2") (pinfunction "2_2") (pintype "passive"))
      (node (ref "C15") (pin "2") (pinfunction "2_2") (pintype "passive"))
      (node (ref "C16") (pin "2") (pinfunction "2_2") (pintype "passive"))
      (node (ref "C17") (pin "2") (pinfunction "2_2") (pintype "passive"))
      (node (ref "C18") (pin "2") (pinfunction "2_2") (pintype "passive"))
      (node (ref "C19") (pin "2") (pinfunction "2_2") (pintype "passive"))
      (node (ref "C2") (pin "2") (pinfunction "2_2") (pintype "passive"))
      (node (ref "C20") (pin "2") (pinfunction "2_2") (pintype "passive"))
      (node (ref "C21") (pin "2") (pinfunction "2_2") (pintype "passive"))
      (node (ref "C3") (pin "2") (pinfunction "2_2") (pintype "passive"))
      (node (ref "C4") (pin "2") (pinfunction "2_2") (pintype "passive"))
      (node (ref "C5") (pin "2") (pinfunction "2_2") (pintype "passive"))
      (node (ref "C6") (pin "2") (pinfunction "2_2") (pintype "passive"))
      (node (ref "C7") (pin "2") (pinfunction "2_2") (pintype "passive"))
      (node (ref "C8") (pin "2") (pinfunction "2_2") (pintype "passive"))
      (node (ref "C9") (pin "2") (pinfunction "2_2") (pintype "passive"))
      (node (ref "D2") (pin "3") (pinfunction "GND_3") (pintype "power_in"))
      (node (ref "D2") (pin "8") (pinfunction "GND_8") (pintype "power_in"))
      (node (ref "D3") (pin "3") (pinfunction "GND_3") (pintype "power_in"))
      (node (ref "D3") (pin "8") (pinfunction "GND_8") (pintype "power_in"))
      (node (ref "D4") (pin "3") (pinfunction "GND_3") (pintype "power_in"))
      (node (ref "D4") (pin "8") (pinfunction "GND_8") (pintype "power_in"))
      (node (ref "D5") (pin "3") (pinfunction "GND_3") (pintype "power_in"))
      (node (ref "D5") (pin "8") (pinfunction "GND_8") (pintype "power_in"))
      (node (ref "D6") (pin "3") (pinfunction "GND_3") (pintype "power_in"))
      (node (ref "D6") (pin "8") (pinfunction "GND_8") (pintype "power_in"))
      (node (ref "D7") (pin "3") (pinfunction "GND_3") (pintype "power_in"))
      (node (ref "D7") (pin "8") (pinfunction "GND_8") (pintype "power_in"))
      (node (ref "J1") (pin "2") (pinfunction "2_2") (pintype "passive"))
      (node (ref "J19") (pin "1") (pinfunction "1_1") (pintype "passive"))
      (node (ref "J2") (pin "2") (pinfunction "2_2") (pintype "passive"))
      (node (ref "J2") (pin "3") (pinfunction "3_3") (pintype "passive"))
      (node (ref "MH1") (pin "1") (pinfunction "MH_1") (pintype "passive"))
      (node (ref "MH1") (pin "2") (pinfunction "V1_2") (pintype "passive"))
      (node (ref "MH1") (pin "3") (pinfunction "V2_3") (pintype "passive"))
      (node (ref "MH1") (pin "4") (pinfunction "V3_4") (pintype "passive"))
      (node (ref "MH1") (pin "5") (pinfunction "V4_5") (pintype "passive"))
      (node (ref "MH1") (pin "6") (pinfunction "V5_6") (pintype "passive"))
      (node (ref "MH1") (pin "7") (pinfunction "V6_7") (pintype "passive"))
      (node (ref "MH2") (pin "1") (pinfunction "MH_1") (pintype "passive"))
      (node (ref "MH2") (pin "2") (pinfunction "V1_2") (pintype "passive"))
      (node (ref "MH2") (pin "3") (pinfunction "V2_3") (pintype "passive"))
      (node (ref "MH2") (pin "4") (pinfunction "V3_4") (pintype "passive"))
      (node (ref "MH2") (pin "5") (pinfunction "V4_5") (pintype "passive"))
      (node (ref "MH2") (pin "6") (pinfunction "V5_6") (pintype "passive"))
      (node (ref "MH2") (pin "7") (pinfunction "V6_7") (pintype "passive"))
      (node (ref "MH3") (pin "1") (pinfunction "MH_1") (pintype "passive"))
      (node (ref "MH3") (pin "2") (pinfunction "V1_2") (pintype "passive"))
      (node (ref "MH3") (pin "3") (pinfunction "V2_3") (pintype "passive"))
      (node (ref "MH3") (pin "4") (pinfunction "V3_4") (pintype "passive"))
      (node (ref "MH3") (pin "5") (pinfunction "V4_5") (pintype "passive"))
      (node (ref "MH3") (pin "6") (pinfunction "V5_6") (pintype "passive"))
      (node (ref "MH3") (pin "7") (pinfunction "V6_7") (pintype "passive"))
      (node (ref "MH4") (pin "1") (pinfunction "MH_1") (pintype "passive"))
      (node (ref "MH4") (pin "2") (pinfunction "V1_2") (pintype "passive"))
      (node (ref "MH4") (pin "3") (pinfunction "V2_3") (pintype "passive"))
      (node (ref "MH4") (pin "4") (pinfunction "V3_4") (pintype "passive"))
      (node (ref "MH4") (pin "5") (pinfunction "V4_5") (pintype "passive"))
      (node (ref "MH4") (pin "6") (pinfunction "V5_6") (pintype "passive"))
      (node (ref "MH4") (pin "7") (pinfunction "V6_7") (pintype "passive"))
      (node (ref "MH5") (pin "1") (pinfunction "MH_1") (pintype "passive"))
      (node (ref "MH5") (pin "2") (pinfunction "V1_2") (pintype "passive"))
      (node (ref "MH5") (pin "3") (pinfunction "V2_3") (pintype "passive"))
      (node (ref "MH5") (pin "4") (pinfunction "V3_4") (pintype "passive"))
      (node (ref "MH5") (pin "5") (pinfunction "V4_5") (pintype "passive"))
      (node (ref "MH5") (pin "6") (pinfunction "V5_6") (pintype "passive"))
      (node (ref "MH5") (pin "7") (pinfunction "V6_7") (pintype "passive"))
      (node (ref "MH6") (pin "1") (pinfunction "MH_1") (pintype "passive"))
      (node (ref "MH6") (pin "2") (pinfunction "V1_2") (pintype "passive"))
      (node (ref "MH6") (pin "3") (pinfunction "V2_3") (pintype "passive"))
      (node (ref "MH6") (pin "4") (pinfunction "V3_4") (pintype "passive"))
      (node (ref "MH6") (pin "5") (pinfunction "V4_5") (pintype "passive"))
      (node (ref "MH6") (pin "6") (pinfunction "V5_6") (pintype "passive"))
      (node (ref "MH6") (pin "7") (pinfunction "V6_7") (pintype "passive"))
      (node (ref "MH7") (pin "1") (pinfunction "MH_1") (pintype "passive"))
      (node (ref "MH7") (pin "2") (pinfunction "V1_2") (pintype "passive"))
      (node (ref "MH7") (pin "3") (pinfunction "V2_3") (pintype "passive"))
      (node (ref "MH7") (pin "4") (pinfunction "V3_4") (pintype "passive"))
      (node (ref "MH7") (pin "5") (pinfunction "V4_5") (pintype "passive"))
      (node (ref "MH7") (pin "6") (pinfunction "V5_6") (pintype "passive"))
      (node (ref "MH7") (pin "7") (pinfunction "V6_7") (pintype "passive"))
      (node (ref "MH8") (pin "1") (pinfunction "MH_1") (pintype "passive"))
      (node (ref "MH8") (pin "2") (pinfunction "V1_2") (pintype "passive"))
      (node (ref "MH8") (pin "3") (pinfunction "V2_3") (pintype "passive"))
      (node (ref "MH8") (pin "4") (pinfunction "V3_4") (pintype "passive"))
      (node (ref "MH8") (pin "5") (pinfunction "V4_5") (pintype "passive"))
      (node (ref "MH8") (pin "6") (pinfunction "V5_6") (pintype "passive"))
      (node (ref "MH8") (pin "7") (pinfunction "V6_7") (pintype "passive"))
      (node (ref "R1") (pin "1") (pinfunction "1_1") (pintype "passive"))
    )
    (net (code "124") (name "Net-(D1-A)") (class "Default")
      (node (ref "D1") (pin "2") (pinfunction "A_2") (pintype "passive"))
      (node (ref "Q1") (pin "4") (pinfunction "G_4") (pintype "passive"))
      (node (ref "R1") (pin "2") (pinfunction "2_2") (pintype "passive"))
    )
    (net (code "125") (name "Net-(D10-A-Pad2)") (class "Default")
      (node (ref "D10") (pin "2") (pinfunction "A_2") (pintype "passive"))
      (node (ref "R50") (pin "1") (pinfunction "1_1") (pintype "passive"))
    )
    (net (code "126") (name "Net-(D10-A-Pad3)") (class "Default")
      (node (ref "D10") (pin "3") (pinfunction "A_3") (pintype "passive"))
      (node (ref "R51") (pin "1") (pinfunction "1_1") (pintype "passive"))
    )
    (net (code "127") (name "Net-(F1-Pad1)") (class "Default")
      (node (ref "F1") (pin "1") (pinfunction "1_1") (pintype "passive"))
      (node (ref "J1") (pin "1") (pinfunction "1_1") (pintype "passive"))
      (node (ref "J2") (pin "1") (pinfunction "1_1") (pintype "passive"))
    )
    (net (code "128") (name "Net-(J3-PadL1)") (class "Default")
      (node (ref "J3") (pin "L1") (pinfunction "L1_L1") (pintype "passive"))
      (node (ref "R3") (pin "2") (pinfunction "2_2") (pintype "passive"))
    )
    (net (code "129") (name "Net-(J3-PadL3)") (class "Default")
      (node (ref "J3") (pin "L3") (pinfunction "L3_L3") (pintype "passive"))
      (node (ref "R2") (pin "2") (pinfunction "2_2") (pintype "passive"))
    )
    (net (code "130") (name "Net-(J3-TCT)") (class "Default")
      (node (ref "C1") (pin "1") (pinfunction "1_1") (pintype "passive"))
      (node (ref "J3") (pin "P6") (pinfunction "TCT_P6") (pintype "passive"))
    )
    (net (code "131") (name "Net-(Q1-D)") (class "Default")
      (node (ref "F1") (pin "2") (pinfunction "2_2") (pintype "passive"))
      (node (ref "Q1") (pin "5-6-7-8") (pinfunction "D_5-6-7-8") (pintype "passive"))
    )
    (net (code "132") (name "P1_GND") (class "Default")
      (node (ref "C2") (pin "1") (pinfunction "1_1") (pintype "passive"))
      (node (ref "C3") (pin "1") (pinfunction "1_1") (pintype "passive"))
      (node (ref "C4") (pin "1") (pinfunction "1_1") (pintype "passive"))
      (node (ref "C5") (pin "1") (pinfunction "1_1") (pintype "passive"))
      (node (ref "J4") (pin "3") (pinfunction "SHIELD_3") (pintype "passive"))
    )
    (net (code "133") (name "P2_GND") (class "Default")
      (node (ref "C11") (pin "1") (pinfunction "1_1") (pintype "passive"))
      (node (ref "C13") (pin "1") (pinfunction "1_1") (pintype "passive"))
      (node (ref "C7") (pin "1") (pinfunction "1_1") (pintype "passive"))
      (node (ref "C9") (pin "1") (pinfunction "1_1") (pintype "passive"))
      (node (ref "J5") (pin "3") (pinfunction "SHIELD_3") (pintype "passive"))
    )
    (net (code "134") (name "P3_GND") (class "Default")
      (node (ref "C14") (pin "1") (pinfunction "1_1") (pintype "passive"))
      (node (ref "C15") (pin "1") (pinfunction "1_1") (pintype "passive"))
      (node (ref "C16") (pin "1") (pinfunction "1_1") (pintype "passive"))
      (node (ref "C17") (pin "1") (pinfunction "1_1") (pintype "passive"))
      (node (ref "J6") (pin "3") (pinfunction "SHIELD_3") (pintype "passive"))
    )
    (net (code "135") (name "P4_GND") (class "Default")
      (node (ref "C18") (pin "1") (pinfunction "1_1") (pintype "passive"))
      (node (ref "C19") (pin "1") (pinfunction "1_1") (pintype "passive"))
      (node (ref "C20") (pin "1") (pinfunction "1_1") (pintype "passive"))
      (node (ref "C21") (pin "1") (pinfunction "1_1") (pintype "passive"))
      (node (ref "J7") (pin "3") (pinfunction "SHIELD_3") (pintype "passive"))
    )
    (net (code "136") (name "RJ45_GND") (class "Default")
      (node (ref "C1") (pin "2") (pinfunction "2_2") (pintype "passive"))
      (node (ref "C10") (pin "1") (pinfunction "1_1") (pintype "passive"))
      (node (ref "C12") (pin "1") (pinfunction "1_1") (pintype "passive"))
      (node (ref "C6") (pin "1") (pinfunction "1_1") (pintype "passive"))
      (node (ref "C8") (pin "1") (pinfunction "1_1") (pintype "passive"))
      (node (ref "J3") (pin "P1") (pinfunction "GND_P1") (pintype "power_in"))
      (node (ref "J3") (pin "S1") (pinfunction "SHIELD_S1") (pintype "passive"))
      (node (ref "J3") (pin "S2") (pinfunction "SHIELD_S2") (pintype "passive"))
    )
    (net (code "137") (name "VCC") (class "Default")
      (node (ref "D1") (pin "1") (pinfunction "K_1") (pintype "passive"))
      (node (ref "J10") (pin "1") (pinfunction "1_1") (pintype "passive"))
      (node (ref "Q1") (pin "1") (pinfunction "S_1") (pintype "passive"))
      (node (ref "Q1") (pin "2") (pinfunction "S_2") (pintype "passive"))
      (node (ref "Q1") (pin "3") (pinfunction "S_3") (pintype "passive"))
    )
    (net (code "138") (name "unconnected-(D4-IO1-Pad1)") (class "Default")
      (node (ref "D4") (pin "1") (pinfunction "IO1_1") (pintype "bidirectional+no_connect"))
    )
    (net (code "139") (name "unconnected-(D4-IO4-Pad5)") (class "Default")
      (node (ref "D4") (pin "5") (pinfunction "IO4_5") (pintype "bidirectional+no_connect"))
    )
    (net (code "140") (name "unconnected-(D4-NC-Pad6)") (class "Default")
      (node (ref "D4") (pin "6") (pinfunction "NC_6") (pintype "passive+no_connect"))
    )
    (net (code "141") (name "unconnected-(D4-NC-Pad10)") (class "Default")
      (node (ref "D4") (pin "10") (pinfunction "NC_10") (pintype "passive+no_connect"))
    )
    (net (code "142") (name "unconnected-(D5-IO1-Pad1)") (class "Default")
      (node (ref "D5") (pin "1") (pinfunction "IO1_1") (pintype "bidirectional+no_connect"))
    )
    (net (code "143") (name "unconnected-(D5-IO4-Pad5)") (class "Default")
      (node (ref "D5") (pin "5") (pinfunction "IO4_5") (pintype "bidirectional+no_connect"))
    )
    (net (code "144") (name "unconnected-(D5-NC-Pad6)") (class "Default")
      (node (ref "D5") (pin "6") (pinfunction "NC_6") (pintype "passive+no_connect"))
    )
    (net (code "145") (name "unconnected-(D5-NC-Pad10)") (class "Default")
      (node (ref "D5") (pin "10") (pinfunction "NC_10") (pintype "passive+no_connect"))
    )
    (net (code "146") (name "unconnected-(D6-IO1-Pad1)") (class "Default")
      (node (ref "D6") (pin "1") (pinfunction "IO1_1") (pintype "bidirectional+no_connect"))
    )
    (net (code "147") (name "unconnected-(D6-IO4-Pad5)") (class "Default")
      (node (ref "D6") (pin "5") (pinfunction "IO4_5") (pintype "bidirectional+no_connect"))
    )
    (net (code "148") (name "unconnected-(D6-NC-Pad6)") (class "Default")
      (node (ref "D6") (pin "6") (pinfunction "NC_6") (pintype "passive+no_connect"))
    )
    (net (code "149") (name "unconnected-(D6-NC-Pad10)") (class "Default")
      (node (ref "D6") (pin "10") (pinfunction "NC_10") (pintype "passive+no_connect"))
    )
    (net (code "150") (name "unconnected-(D7-IO1-Pad1)") (class "Default")
      (node (ref "D7") (pin "1") (pinfunction "IO1_1") (pintype "bidirectional+no_connect"))
    )
    (net (code "151") (name "unconnected-(D7-IO4-Pad5)") (class "Default")
      (node (ref "D7") (pin "5") (pinfunction "IO4_5") (pintype "bidirectional+no_connect"))
    )
    (net (code "152") (name "unconnected-(D7-NC-Pad6)") (class "Default")
      (node (ref "D7") (pin "6") (pinfunction "NC_6") (pintype "passive+no_connect"))
    )
    (net (code "153") (name "unconnected-(D7-NC-Pad10)") (class "Default")
      (node (ref "D7") (pin "10") (pinfunction "NC_10") (pintype "passive+no_connect"))
    )
  )
)
